# tinyha_doorbell.net
KiCad netlist of a schematic drawn in EAGLE
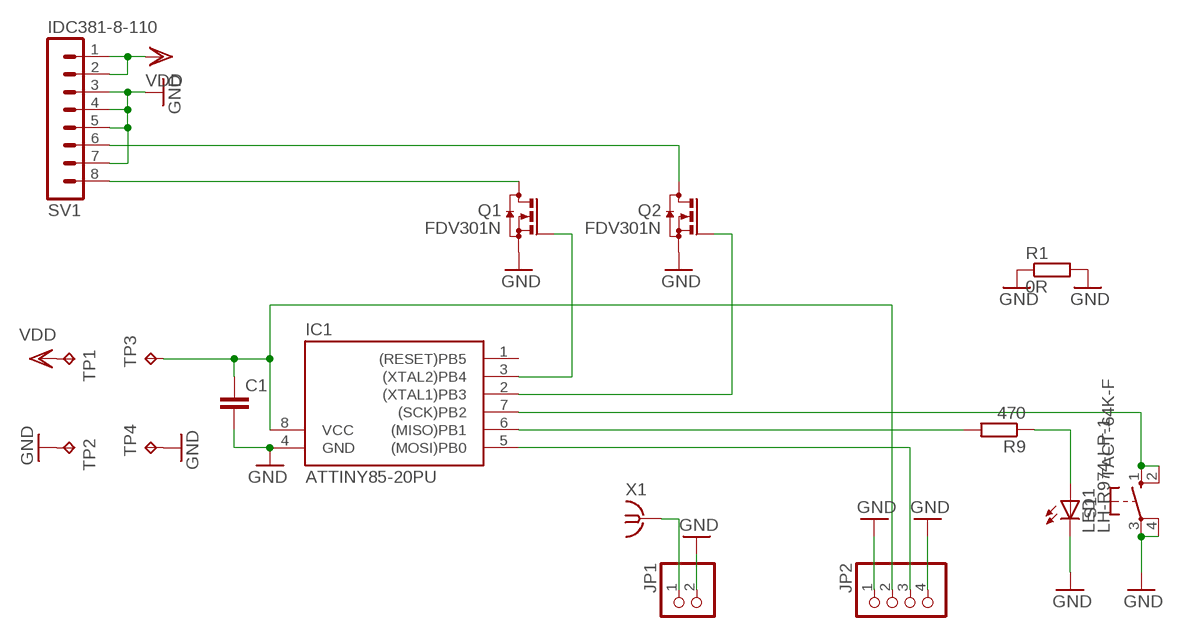
[diagram p0: schematic, sheet 1]

(export (version "E")
  (design (tool "Eeschema 10.0.6"))
  (components
    (comp (ref "C1")
      (value "C-EUC0805K")
      (footprint "eagle-import:C0805K")
      (libsource (lib "eagle-import") (part "C-EUC0805K"))
    )
    (comp (ref "IC1")
      (value "ATTINY85-20PU")
      (footprint "eagle-import:DIL08")
      (libsource (lib "eagle-import") (part "TINY12P"))
    )
    (comp (ref "JP1")
      (value "PINHD-1X2")
      (footprint "eagle-import:1X02")
      (libsource (lib "eagle-import") (part "PINHD-1X2"))
    )
    (comp (ref "JP2")
      (value "PINHD-1X4")
      (footprint "eagle-import:1X04")
      (libsource (lib "eagle-import") (part "PINHD-1X4"))
    )
    (comp (ref "LED1")
      (value "LH-R974-LP-1")
      (footprint "eagle-import:LED3MM")
      (libsource (lib "eagle-import") (part "LED3MM"))
    )
    (comp (ref "Q1")
      (value "FDV301N")
      (footprint "eagle-import:SOT23")
      (libsource (lib "eagle-import") (part "BSS123"))
    )
    (comp (ref "Q2")
      (value "FDV301N")
      (footprint "eagle-import:SOT23")
      (libsource (lib "eagle-import") (part "BSS123"))
    )
    (comp (ref "R1")
      (value "0R")
      (footprint "eagle-import:R1206")
      (libsource (lib "eagle-import") (part "R-EU_R1206"))
    )
    (comp (ref "R9")
      (value "470")
      (footprint "eagle-import:R0805")
      (libsource (lib "eagle-import") (part "R-EU_R0805"))
    )
    (comp (ref "S1")
      (value "TACT-64K-F")
      (footprint "eagle-import:B3F-10XX")
      (fields (field (name "MPN") "B3F-1000"))
      (libsource (lib "eagle-import") (part "10-XX"))
    )
    (comp (ref "SV1")
      (value "IDC381-8-110")
      (footprint "eagle-import:IDC381-8")
      (libsource (lib "eagle-import") (part "MA08-1-IDC"))
    )
    (comp (ref "TP1")
      (value "TPPAD1-13Y")
      (footprint "eagle-import:P1-13Y")
      (libsource (lib "eagle-import") (part "TPPAD1-13Y"))
    )
    (comp (ref "TP2")
      (value "TPPAD1-13Y")
      (footprint "eagle-import:P1-13Y")
      (libsource (lib "eagle-import") (part "TPPAD1-13Y"))
    )
    (comp (ref "TP3")
      (value "TPPAD1-13Y")
      (footprint "eagle-import:P1-13Y")
      (libsource (lib "eagle-import") (part "TPPAD1-13Y"))
    )
    (comp (ref "TP4")
      (value "TPPAD1-13Y")
      (footprint "eagle-import:P1-13Y")
      (libsource (lib "eagle-import") (part "TPPAD1-13Y"))
    )
    (comp (ref "X1")
      (value "SMA-DX-V")
      (footprint "eagle-import:BU-SMA-V")
      (libsource (lib "eagle-import") (part "SMA-DX-V"))
    )
  )
  (nets
    (net (code "1") (name "GND") (class "Default")
      (node (ref "C1") (pin "2") (pinfunction "2_2") (pintype "passive"))
      (node (ref "IC1") (pin "4") (pinfunction "GND_4") (pintype "power_in"))
      (node (ref "JP1") (pin "2") (pinfunction "2_2") (pintype "passive"))
      (node (ref "JP2") (pin "1") (pinfunction "1_1") (pintype "passive"))
      (node (ref "JP2") (pin "4") (pinfunction "4_4") (pintype "passive"))
      (node (ref "LED1") (pin "K") (pinfunction "C_K") (pintype "passive"))
      (node (ref "Q1") (pin "2") (pinfunction "S_2") (pintype "passive"))
      (node (ref "Q2") (pin "2") (pinfunction "S_2") (pintype "passive"))
      (node (ref "R1") (pin "1") (pinfunction "1_1") (pintype "passive"))
      (node (ref "R1") (pin "2") (pinfunction "2_2") (pintype "passive"))
      (node (ref "S1") (pin "3") (pinfunction "P_3") (pintype "passive"))
      (node (ref "S1") (pin "4") (pinfunction "P1_4") (pintype "passive"))
      (node (ref "SV1") (pin "3") (pinfunction "3_3") (pintype "passive"))
      (node (ref "SV1") (pin "4") (pinfunction "4_4") (pintype "passive"))
      (node (ref "SV1") (pin "5") (pinfunction "5_5") (pintype "passive"))
      (node (ref "SV1") (pin "7") (pinfunction "7_7") (pintype "passive"))
      (node (ref "TP2") (pin "TP") (pinfunction "TP_TP") (pintype "input"))
      (node (ref "TP4") (pin "TP") (pinfunction "TP_TP") (pintype "input"))
    )
    (net (code "2") (name "Net-(IC1-(MISO)PB1)") (class "Default")
      (node (ref "IC1") (pin "6") (pinfunction "(MISO)PB1_6") (pintype "bidirectional"))
      (node (ref "R9") (pin "2") (pinfunction "2_2") (pintype "passive"))
    )
    (net (code "3") (name "Net-(IC1-(MOSI)PB0)") (class "Default")
      (node (ref "IC1") (pin "5") (pinfunction "(MOSI)PB0_5") (pintype "bidirectional"))
      (node (ref "JP2") (pin "3") (pinfunction "3_3") (pintype "passive"))
    )
    (net (code "4") (name "Net-(IC1-(SCK)PB2)") (class "Default")
      (node (ref "IC1") (pin "7") (pinfunction "(SCK)PB2_7") (pintype "bidirectional"))
      (node (ref "S1") (pin "1") (pinfunction "S_1") (pintype "passive"))
      (node (ref "S1") (pin "2") (pinfunction "S1_2") (pintype "passive"))
    )
    (net (code "5") (name "Net-(IC1-(XTAL1)PB3)") (class "Default")
      (node (ref "IC1") (pin "2") (pinfunction "(XTAL1)PB3_2") (pintype "bidirectional"))
      (node (ref "Q2") (pin "1") (pinfunction "G_1") (pintype "passive"))
    )
    (net (code "6") (name "Net-(IC1-(XTAL2)PB4)") (class "Default")
      (node (ref "IC1") (pin "3") (pinfunction "(XTAL2)PB4_3") (pintype "bidirectional"))
      (node (ref "Q1") (pin "1") (pinfunction "G_1") (pintype "passive"))
    )
    (net (code "7") (name "Net-(IC1-VCC)") (class "Default")
      (node (ref "C1") (pin "1") (pinfunction "1_1") (pintype "passive"))
      (node (ref "IC1") (pin "8") (pinfunction "VCC_8") (pintype "power_in"))
      (node (ref "JP2") (pin "2") (pinfunction "2_2") (pintype "passive"))
      (node (ref "TP3") (pin "TP") (pinfunction "TP_TP") (pintype "input"))
    )
    (net (code "8") (name "Net-(JP1-Pad1)") (class "Default")
      (node (ref "JP1") (pin "1") (pinfunction "1_1") (pintype "passive"))
      (node (ref "X1") (pin "1") (pinfunction "1_1") (pintype "passive"))
    )
    (net (code "9") (name "Net-(LED1-PadA)") (class "Default")
      (node (ref "LED1") (pin "A") (pinfunction "A_A") (pintype "passive"))
      (node (ref "R9") (pin "1") (pinfunction "1_1") (pintype "passive"))
    )
    (net (code "10") (name "Net-(Q1-D)") (class "Default")
      (node (ref "Q1") (pin "3") (pinfunction "D_3") (pintype "passive"))
      (node (ref "SV1") (pin "8") (pinfunction "8_8") (pintype "passive"))
    )
    (net (code "11") (name "Net-(Q2-D)") (class "Default")
      (node (ref "Q2") (pin "3") (pinfunction "D_3") (pintype "passive"))
      (node (ref "SV1") (pin "6") (pinfunction "6_6") (pintype "passive"))
    )
    (net (code "12") (name "VDD") (class "Default")
      (node (ref "SV1") (pin "1") (pinfunction "1_1") (pintype "passive"))
      (node (ref "SV1") (pin "2") (pinfunction "2_2") (pintype "passive"))
      (node (ref "TP1") (pin "TP") (pinfunction "TP_TP") (pintype "input"))
    )
    (net (code "13") (name "unconnected-(IC1-(RESET)PB5-Pad1)") (class "Default")
      (node (ref "IC1") (pin "1") (pinfunction "(RESET)PB5_1") (pintype "bidirectional"))
    )
  )
)
